# Three_Phase_Inverter_Based_on_IR2111_Gat.net
KiCad netlist of a schematic drawn in Altium Designer
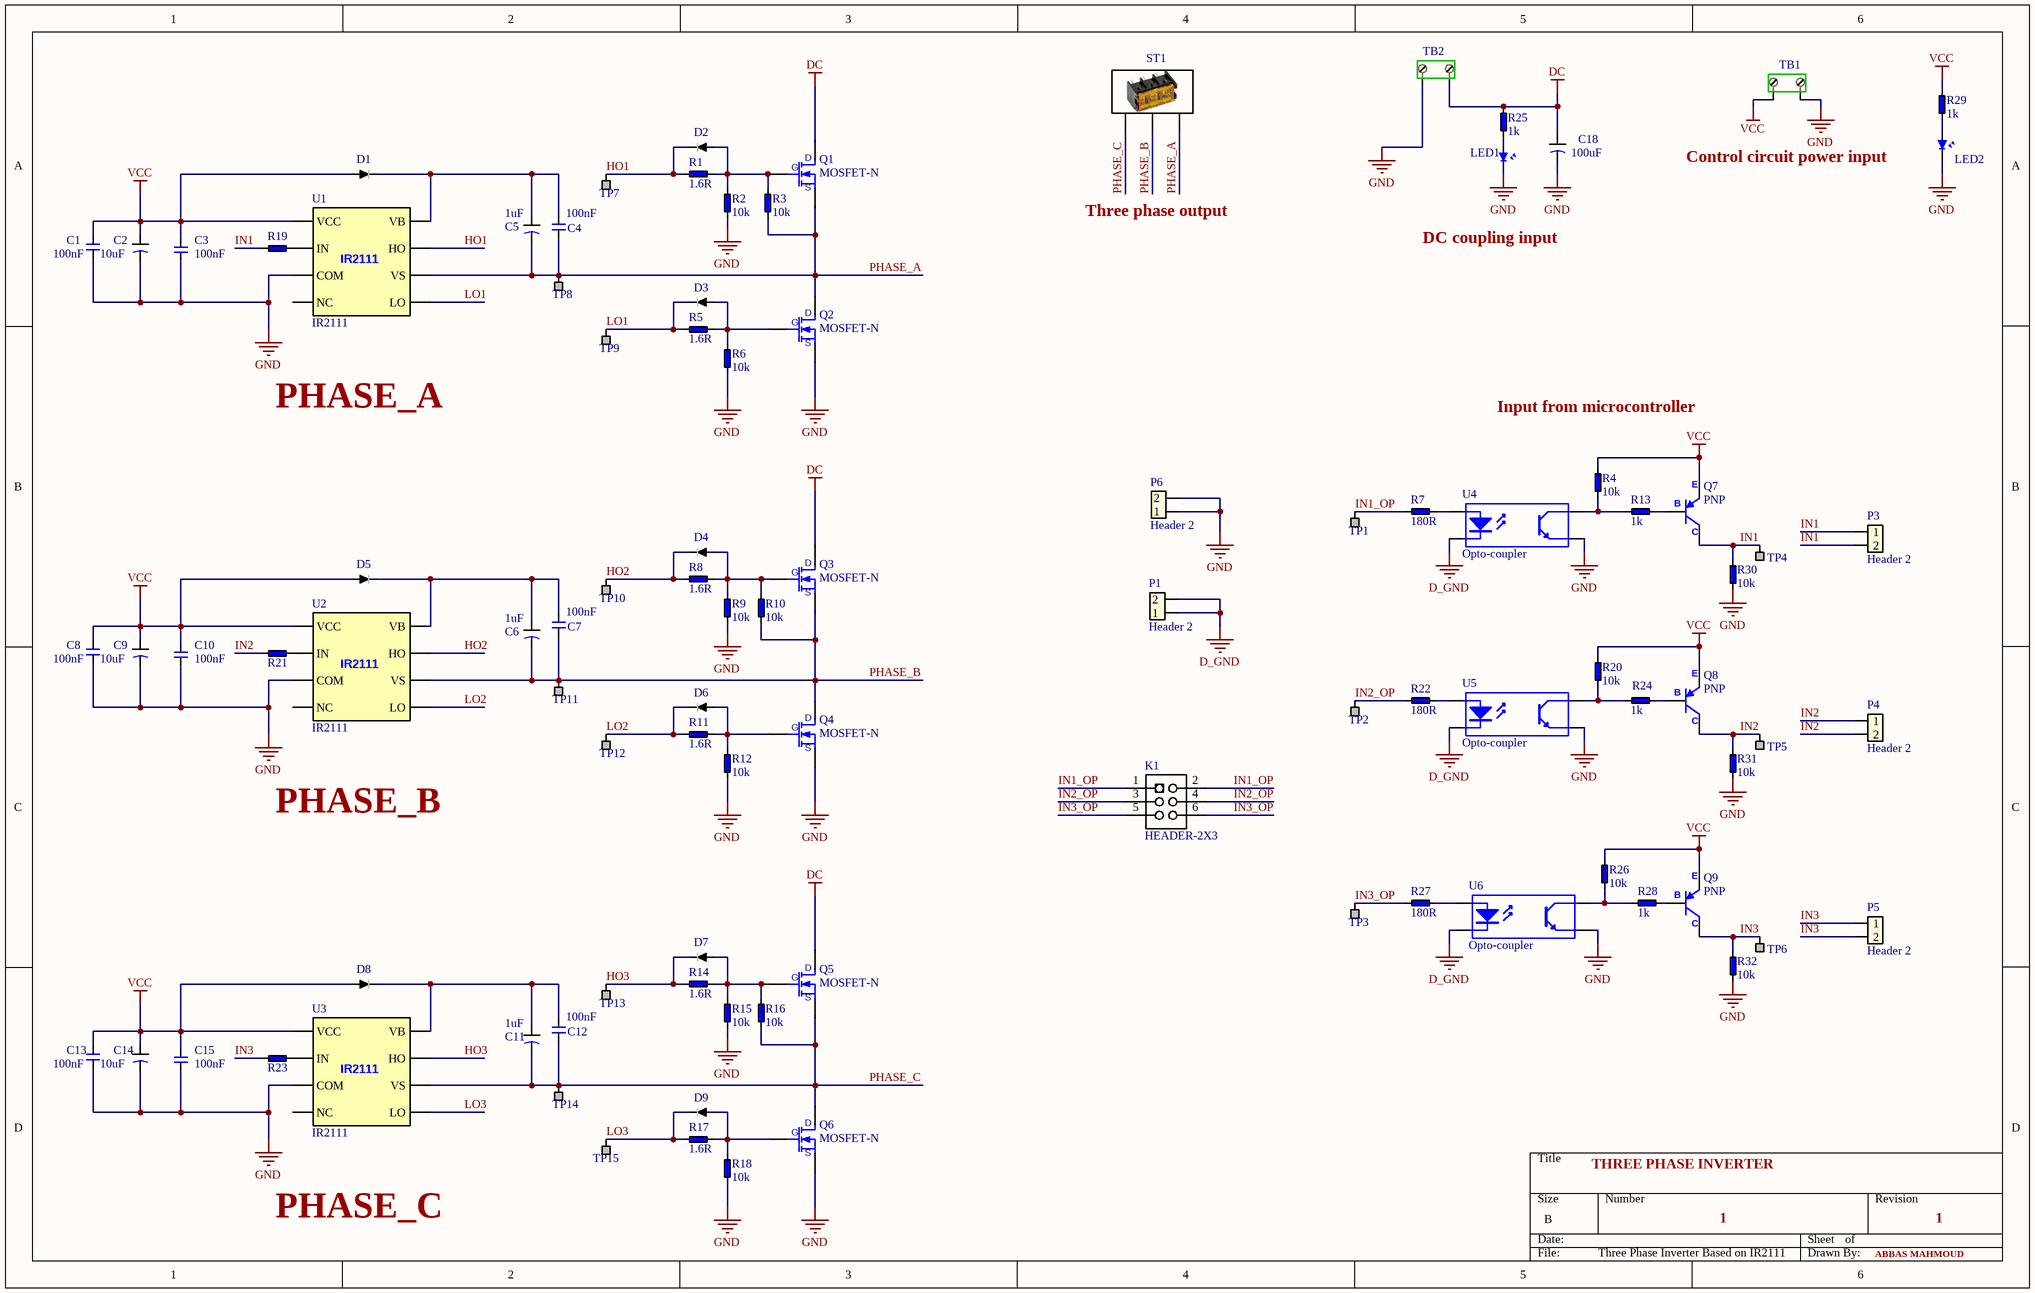
[diagram p0: Three Phase Inverter Based on IR2111 Gate Driver.SchDoc]

(export (version "E")
  (design (tool "Eeschema 10.0.6"))
  (components
    (comp (ref "C1")
      (value "100nF")
      (footprint "CCAP 0.1 P Y")
      (libsource (lib "Altium_Abbas") (part "CERAMIC CAP"))
    )
    (comp (ref "C2")
      (value "10uF")
      (footprint "ECAP 5X11X2MM")
      (libsource (lib "Altium_Abbas") (part "CAP POL"))
    )
    (comp (ref "C3")
      (value "100nF")
      (footprint "CCAP 0.1 P Y")
      (libsource (lib "Altium_Abbas") (part "CERAMIC CAP"))
    )
    (comp (ref "C4")
      (value "100nF")
      (footprint "CCAP 0.1 P Y")
      (libsource (lib "Altium_Abbas") (part "CERAMIC CAP"))
    )
    (comp (ref "C5")
      (value "1uF")
      (footprint "ECAP 5X11X2MM")
      (libsource (lib "Altium_Abbas") (part "CAP POL"))
    )
    (comp (ref "C6")
      (value "1uF")
      (footprint "ECAP 5X11X2MM")
      (libsource (lib "Altium_Abbas") (part "CAP POL"))
    )
    (comp (ref "C7")
      (value "100nF")
      (footprint "CCAP 0.1 P Y")
      (libsource (lib "Altium_Abbas") (part "CERAMIC CAP"))
    )
    (comp (ref "C8")
      (value "100nF")
      (footprint "CCAP 0.1 P Y")
      (libsource (lib "Altium_Abbas") (part "CERAMIC CAP"))
    )
    (comp (ref "C9")
      (value "10uF")
      (footprint "ECAP 5X11X2MM")
      (libsource (lib "Altium_Abbas") (part "CAP POL"))
    )
    (comp (ref "C10")
      (value "100nF")
      (footprint "CCAP 0.1 P Y")
      (libsource (lib "Altium_Abbas") (part "CERAMIC CAP"))
    )
    (comp (ref "C11")
      (value "1uF")
      (footprint "ECAP 5X11X2MM")
      (libsource (lib "Altium_Abbas") (part "CAP POL"))
    )
    (comp (ref "C12")
      (value "100nF")
      (footprint "CCAP 0.1 P Y")
      (libsource (lib "Altium_Abbas") (part "CERAMIC CAP"))
    )
    (comp (ref "C13")
      (value "100nF")
      (footprint "CCAP 0.1 P Y")
      (libsource (lib "Altium_Abbas") (part "CERAMIC CAP"))
    )
    (comp (ref "C14")
      (value "10uF")
      (footprint "ECAP 5X11X2MM")
      (libsource (lib "Altium_Abbas") (part "CAP POL"))
    )
    (comp (ref "C15")
      (value "100nF")
      (footprint "CCAP 0.1 P Y")
      (libsource (lib "Altium_Abbas") (part "CERAMIC CAP"))
    )
    (comp (ref "C18")
      (value "100uF")
      (footprint "ECAP 10X20X5MM")
      (libsource (lib "Altium_Abbas") (part "CAP POL"))
    )
    (comp (ref "D1")
      (value "DIODE")
      (footprint "DIODE-1n400X_0.3")
      (libsource (lib "Altium_Abbas") (part "DIODE"))
    )
    (comp (ref "D2")
      (value "DIODE")
      (footprint "DIODE-1n400X_0.3")
      (libsource (lib "Altium_Abbas") (part "DIODE"))
    )
    (comp (ref "D3")
      (value "DIODE")
      (footprint "DIODE-1n400X_0.3")
      (libsource (lib "Altium_Abbas") (part "DIODE"))
    )
    (comp (ref "D4")
      (value "DIODE")
      (footprint "DIODE-1n400X_0.3")
      (libsource (lib "Altium_Abbas") (part "DIODE"))
    )
    (comp (ref "D5")
      (value "DIODE")
      (footprint "DIODE-1n400X_0.3")
      (libsource (lib "Altium_Abbas") (part "DIODE"))
    )
    (comp (ref "D6")
      (value "DIODE")
      (footprint "DIODE-1n400X_0.3")
      (libsource (lib "Altium_Abbas") (part "DIODE"))
    )
    (comp (ref "D7")
      (value "DIODE")
      (footprint "DIODE-1n400X_0.3")
      (libsource (lib "Altium_Abbas") (part "DIODE"))
    )
    (comp (ref "D8")
      (value "DIODE")
      (footprint "DIODE-1n400X_0.3")
      (libsource (lib "Altium_Abbas") (part "DIODE"))
    )
    (comp (ref "D9")
      (value "DIODE")
      (footprint "DIODE-1n400X_0.3")
      (libsource (lib "Altium_Abbas") (part "DIODE"))
    )
    (comp (ref "K1")
      (value "HEADER-2X3")
      (footprint "HEADER-2X3")
      (libsource (lib "vh_altium_library") (part "HEADER-2X3"))
    )
    (comp (ref "LED1") (value "LED") (footprint "LED 3MM RED") (libsource (lib "Altium_Abbas") (part "LED")))
    (comp (ref "LED2")
      (value "LED")
      (footprint "LED 5MM WHITE")
      (libsource (lib "Altium_Abbas") (part "LED"))
    )
    (comp (ref "P1")
      (value "Header 2")
      (footprint "PINHEADER X2")
      (description "Header, 2-Pin")
      (fields (field (name "PUBLISHER") "Altium Limited"))
      (libsource (lib "Altium_Abbas") (part "Header 2"))
    )
    (comp (ref "P3")
      (value "Header 2")
      (footprint "PINHEADER X2")
      (description "Header, 2-Pin")
      (fields (field (name "PUBLISHER") "Altium Limited"))
      (libsource (lib "") (part "Header 2_1"))
    )
    (comp (ref "P4")
      (value "Header 2")
      (footprint "PINHEADER X2")
      (description "Header, 2-Pin")
      (fields (field (name "PUBLISHER") "Altium Limited"))
      (libsource (lib "") (part "Header 2_1"))
    )
    (comp (ref "P5")
      (value "Header 2")
      (footprint "PINHEADER X2")
      (description "Header, 2-Pin")
      (fields (field (name "PUBLISHER") "Altium Limited"))
      (libsource (lib "") (part "Header 2_1"))
    )
    (comp (ref "P6")
      (value "Header 2")
      (footprint "PINHEADER X2")
      (description "Header, 2-Pin")
      (fields (field (name "PUBLISHER") "Altium Limited"))
      (libsource (lib "Altium_Abbas") (part "Header 2"))
    )
    (comp (ref "Q1")
      (value "MOSFET-N")
      (footprint "Transistor-Mosfet_N_power")
      (description "N CHANNEL MOSFET")
      (libsource (lib "Altium_Abbas") (part "MOSFET-N"))
    )
    (comp (ref "Q2")
      (value "MOSFET-N")
      (footprint "Transistor-Mosfet_N_power")
      (description "N CHANNEL MOSFET")
      (libsource (lib "Altium_Abbas") (part "MOSFET-N"))
    )
    (comp (ref "Q3")
      (value "MOSFET-N")
      (footprint "Transistor-Mosfet_N_power")
      (description "N CHANNEL MOSFET")
      (libsource (lib "Altium_Abbas") (part "MOSFET-N"))
    )
    (comp (ref "Q4")
      (value "MOSFET-N")
      (footprint "Transistor-Mosfet_N_power")
      (description "N CHANNEL MOSFET")
      (libsource (lib "Altium_Abbas") (part "MOSFET-N"))
    )
    (comp (ref "Q5")
      (value "MOSFET-N")
      (footprint "Transistor-Mosfet_N_power")
      (description "N CHANNEL MOSFET")
      (libsource (lib "Altium_Abbas") (part "MOSFET-N"))
    )
    (comp (ref "Q6")
      (value "MOSFET-N")
      (footprint "Transistor-Mosfet_N_power")
      (description "N CHANNEL MOSFET")
      (libsource (lib "Altium_Abbas") (part "MOSFET-N"))
    )
    (comp (ref "Q7")
      (value "PNP")
      (footprint "Transistor - duplicate3")
      (libsource (lib "Altium_Abbas") (part "PNP"))
    )
    (comp (ref "Q8")
      (value "PNP")
      (footprint "Transistor - duplicate3")
      (libsource (lib "Altium_Abbas") (part "PNP"))
    )
    (comp (ref "Q9")
      (value "PNP")
      (footprint "Transistor - duplicate3")
      (libsource (lib "Altium_Abbas") (part "PNP"))
    )
    (comp (ref "R1")
      (value "1.6R")
      (footprint "RESISTOR _1")
      (libsource (lib "Altium_Abbas") (part "RESISTOR"))
    )
    (comp (ref "R2")
      (value "10k")
      (footprint "RESISTOR _1")
      (libsource (lib "Altium_Abbas") (part "RESISTOR"))
    )
    (comp (ref "R3")
      (value "10k")
      (footprint "RESISTOR _1")
      (libsource (lib "Altium_Abbas") (part "RESISTOR"))
    )
    (comp (ref "R4")
      (value "10k")
      (footprint "RESISTOR _1")
      (libsource (lib "Altium_Abbas") (part "RESISTOR"))
    )
    (comp (ref "R5")
      (value "1.6R")
      (footprint "RESISTOR _1")
      (libsource (lib "Altium_Abbas") (part "RESISTOR"))
    )
    (comp (ref "R6")
      (value "10k")
      (footprint "RESISTOR _1")
      (libsource (lib "Altium_Abbas") (part "RESISTOR"))
    )
    (comp (ref "R7")
      (value "180R")
      (footprint "RESISTOR _1")
      (libsource (lib "Altium_Abbas") (part "RESISTOR"))
    )
    (comp (ref "R8")
      (value "1.6R")
      (footprint "RESISTOR _1")
      (libsource (lib "Altium_Abbas") (part "RESISTOR"))
    )
    (comp (ref "R9")
      (value "10k")
      (footprint "RESISTOR _1")
      (libsource (lib "Altium_Abbas") (part "RESISTOR"))
    )
    (comp (ref "R10")
      (value "10k")
      (footprint "RESISTOR _1")
      (libsource (lib "Altium_Abbas") (part "RESISTOR"))
    )
    (comp (ref "R11")
      (value "1.6R")
      (footprint "RESISTOR _1")
      (libsource (lib "Altium_Abbas") (part "RESISTOR"))
    )
    (comp (ref "R12")
      (value "10k")
      (footprint "RESISTOR _1")
      (libsource (lib "Altium_Abbas") (part "RESISTOR"))
    )
    (comp (ref "R13")
      (value "1k")
      (footprint "RESISTOR _1")
      (libsource (lib "Altium_Abbas") (part "RESISTOR"))
    )
    (comp (ref "R14")
      (value "1.6R")
      (footprint "RESISTOR _1")
      (libsource (lib "Altium_Abbas") (part "RESISTOR"))
    )
    (comp (ref "R15")
      (value "10k")
      (footprint "RESISTOR _1")
      (libsource (lib "Altium_Abbas") (part "RESISTOR"))
    )
    (comp (ref "R16")
      (value "10k")
      (footprint "RESISTOR _1")
      (libsource (lib "Altium_Abbas") (part "RESISTOR"))
    )
    (comp (ref "R17")
      (value "1.6R")
      (footprint "RESISTOR _1")
      (libsource (lib "Altium_Abbas") (part "RESISTOR"))
    )
    (comp (ref "R18")
      (value "10k")
      (footprint "RESISTOR _1")
      (libsource (lib "Altium_Abbas") (part "RESISTOR"))
    )
    (comp (ref "R19")
      (value "1k")
      (footprint "RESISTOR _1")
      (libsource (lib "Altium_Abbas") (part "RESISTOR"))
    )
    (comp (ref "R20")
      (value "10k")
      (footprint "RESISTOR _1")
      (libsource (lib "Altium_Abbas") (part "RESISTOR"))
    )
    (comp (ref "R21")
      (value "1k")
      (footprint "RESISTOR _1")
      (libsource (lib "Altium_Abbas") (part "RESISTOR"))
    )
    (comp (ref "R22")
      (value "180R")
      (footprint "RESISTOR _1")
      (libsource (lib "Altium_Abbas") (part "RESISTOR"))
    )
    (comp (ref "R23")
      (value "1k")
      (footprint "RESISTOR _1")
      (libsource (lib "Altium_Abbas") (part "RESISTOR"))
    )
    (comp (ref "R24")
      (value "1k")
      (footprint "RESISTOR _1")
      (libsource (lib "Altium_Abbas") (part "RESISTOR"))
    )
    (comp (ref "R25")
      (value "1k")
      (footprint "RESISTOR _9")
      (libsource (lib "Altium_Abbas") (part "RESISTOR"))
    )
    (comp (ref "R26")
      (value "10k")
      (footprint "RESISTOR _1")
      (libsource (lib "Altium_Abbas") (part "RESISTOR"))
    )
    (comp (ref "R27")
      (value "180R")
      (footprint "RESISTOR _1")
      (libsource (lib "Altium_Abbas") (part "RESISTOR"))
    )
    (comp (ref "R28")
      (value "1k")
      (footprint "RESISTOR _1")
      (libsource (lib "Altium_Abbas") (part "RESISTOR"))
    )
    (comp (ref "R29")
      (value "1k")
      (footprint "RESISTOR _9")
      (libsource (lib "Altium_Abbas") (part "RESISTOR"))
    )
    (comp (ref "R30")
      (value "10k")
      (footprint "RESISTOR _1")
      (libsource (lib "Altium_Abbas") (part "RESISTOR"))
    )
    (comp (ref "R31")
      (value "10k")
      (footprint "RESISTOR _1")
      (libsource (lib "Altium_Abbas") (part "RESISTOR"))
    )
    (comp (ref "R32")
      (value "10k")
      (footprint "RESISTOR _1")
      (libsource (lib "Altium_Abbas") (part "RESISTOR"))
    )
    (comp (ref "ST1")
      (value "SCREW TERMINAL x3")
      (footprint "SCREW TERMINAL  x3")
      (description "Barrier Terminal Block 3 Pin with cover 300V/25A")
      (libsource (lib "Altium_Abbas") (part "SCREW TERMINAL x3"))
    )
    (comp (ref "TB1")
      (value "Terminal block 2 pin")
      (footprint "AK500/2 - pluggable")
      (description "Terminal Block 2 Pin 10A 300V")
      (libsource (lib "Altium_Abbas") (part "Terminal block 2 pin"))
    )
    (comp (ref "TB2")
      (value "Terminal block 2 pin")
      (footprint "AK500/2 - pluggable")
      (description "Terminal Block 2 Pin 10A 300V")
      (libsource (lib "Altium_Abbas") (part "Terminal block 2 pin"))
    )
    (comp (ref "TP1")
      (value "TESTPIN")
      (footprint "TESTPIN")
      (description "TESTPIN SINGLE PIN HEADER")
      (libsource (lib "vh_altium_library") (part "TESTPIN"))
    )
    (comp (ref "TP2")
      (value "TESTPIN")
      (footprint "TESTPIN")
      (description "TESTPIN SINGLE PIN HEADER")
      (libsource (lib "vh_altium_library") (part "TESTPIN"))
    )
    (comp (ref "TP3")
      (value "TESTPIN")
      (footprint "TESTPIN")
      (description "TESTPIN SINGLE PIN HEADER")
      (libsource (lib "vh_altium_library") (part "TESTPIN"))
    )
    (comp (ref "TP4")
      (value "TESTPIN")
      (footprint "TESTPIN")
      (description "TESTPIN SINGLE PIN HEADER")
      (libsource (lib "vh_altium_library") (part "TESTPIN"))
    )
    (comp (ref "TP5")
      (value "TESTPIN")
      (footprint "TESTPIN")
      (description "TESTPIN SINGLE PIN HEADER")
      (libsource (lib "vh_altium_library") (part "TESTPIN"))
    )
    (comp (ref "TP6")
      (value "TESTPIN")
      (footprint "TESTPIN")
      (description "TESTPIN SINGLE PIN HEADER")
      (libsource (lib "vh_altium_library") (part "TESTPIN"))
    )
    (comp (ref "TP7")
      (value "TESTPIN")
      (footprint "TESTPIN")
      (description "TESTPIN SINGLE PIN HEADER")
      (libsource (lib "vh_altium_library") (part "TESTPIN"))
    )
    (comp (ref "TP8")
      (value "TESTPIN")
      (footprint "TESTPIN")
      (description "TESTPIN SINGLE PIN HEADER")
      (libsource (lib "vh_altium_library") (part "TESTPIN"))
    )
    (comp (ref "TP9")
      (value "TESTPIN")
      (footprint "TESTPIN")
      (description "TESTPIN SINGLE PIN HEADER")
      (libsource (lib "vh_altium_library") (part "TESTPIN"))
    )
    (comp (ref "TP10")
      (value "TESTPIN")
      (footprint "TESTPIN")
      (description "TESTPIN SINGLE PIN HEADER")
      (libsource (lib "vh_altium_library") (part "TESTPIN"))
    )
    (comp (ref "TP11")
      (value "TESTPIN")
      (footprint "TESTPIN")
      (description "TESTPIN SINGLE PIN HEADER")
      (libsource (lib "vh_altium_library") (part "TESTPIN"))
    )
    (comp (ref "TP12")
      (value "TESTPIN")
      (footprint "TESTPIN")
      (description "TESTPIN SINGLE PIN HEADER")
      (libsource (lib "vh_altium_library") (part "TESTPIN"))
    )
    (comp (ref "TP13")
      (value "TESTPIN")
      (footprint "TESTPIN")
      (description "TESTPIN SINGLE PIN HEADER")
      (libsource (lib "vh_altium_library") (part "TESTPIN"))
    )
    (comp (ref "TP14")
      (value "TESTPIN")
      (footprint "TESTPIN")
      (description "TESTPIN SINGLE PIN HEADER")
      (libsource (lib "vh_altium_library") (part "TESTPIN"))
    )
    (comp (ref "TP15")
      (value "TESTPIN")
      (footprint "TESTPIN")
      (description "TESTPIN SINGLE PIN HEADER")
      (libsource (lib "vh_altium_library") (part "TESTPIN"))
    )
    (comp (ref "U1")
      (value "IR2111")
      (footprint "IC X8 PIN")
      (description "HALF-BRIDGE DRIVER")
      (libsource (lib "Altium_Abbas") (part "IR2111"))
    )
    (comp (ref "U2")
      (value "IR2111")
      (footprint "IC X8 PIN")
      (description "HALF-BRIDGE DRIVER")
      (libsource (lib "Altium_Abbas") (part "IR2111"))
    )
    (comp (ref "U3")
      (value "IR2111")
      (footprint "IC X8 PIN")
      (description "HALF-BRIDGE DRIVER")
      (libsource (lib "Altium_Abbas") (part "IR2111"))
    )
    (comp (ref "U4")
      (value "Opto-coupler")
      (footprint "IC X4 PIN")
      (description "4-Pin Phototransistor Optocoupler")
      (fields (field (name "PUBLISHER") "Altium Limited"))
      (libsource (lib "Altium_Abbas") (part "Opto-coupler"))
    )
    (comp (ref "U5")
      (value "Opto-coupler")
      (footprint "IC X4 PIN")
      (description "4-Pin Phototransistor Optocoupler")
      (fields (field (name "PUBLISHER") "Altium Limited"))
      (libsource (lib "Altium_Abbas") (part "Opto-coupler"))
    )
    (comp (ref "U6")
      (value "Opto-coupler")
      (footprint "IC X4 PIN")
      (description "4-Pin Phototransistor Optocoupler")
      (fields (field (name "PUBLISHER") "Altium Limited"))
      (libsource (lib "Altium_Abbas") (part "Opto-coupler"))
    )
  )
  (nets
    (net (code "1") (name "/HO1") (class "Default")
      (node (ref "D2") (pin "K") (pintype "passive"))
      (node (ref "R1") (pin "1") (pinfunction "5_1") (pintype "passive"))
      (node (ref "TP7") (pin "1") (pinfunction "1_1") (pintype "passive"))
      (node (ref "U1") (pin "7") (pinfunction "HO_7") (pintype "passive"))
    )
    (net (code "2") (name "/HO2") (class "Default")
      (node (ref "D4") (pin "K") (pintype "passive"))
      (node (ref "R8") (pin "1") (pinfunction "5_1") (pintype "passive"))
      (node (ref "TP10") (pin "1") (pinfunction "1_1") (pintype "passive"))
      (node (ref "U2") (pin "7") (pinfunction "HO_7") (pintype "passive"))
    )
    (net (code "3") (name "/HO3") (class "Default")
      (node (ref "D7") (pin "K") (pintype "passive"))
      (node (ref "R14") (pin "1") (pinfunction "5_1") (pintype "passive"))
      (node (ref "TP13") (pin "1") (pinfunction "1_1") (pintype "passive"))
      (node (ref "U3") (pin "7") (pinfunction "HO_7") (pintype "passive"))
    )
    (net (code "4") (name "/IN1") (class "Default")
      (node (ref "P3") (pin "1") (pinfunction "1_1") (pintype "passive"))
      (node (ref "P3") (pin "2") (pinfunction "2_2") (pintype "passive"))
      (node (ref "Q7") (pin "3") (pinfunction "C_3") (pintype "passive"))
      (node (ref "R19") (pin "1") (pinfunction "5_1") (pintype "passive"))
      (node (ref "R30") (pin "1") (pinfunction "5_1") (pintype "passive"))
      (node (ref "TP4") (pin "1") (pinfunction "1_1") (pintype "passive"))
    )
    (net (code "5") (name "/IN1_OP") (class "Default")
      (node (ref "K1") (pin "1") (pintype "passive"))
      (node (ref "K1") (pin "2") (pintype "passive"))
      (node (ref "R7") (pin "1") (pinfunction "5_1") (pintype "passive"))
      (node (ref "TP1") (pin "1") (pinfunction "1_1") (pintype "passive"))
    )
    (net (code "6") (name "/IN2") (class "Default")
      (node (ref "P4") (pin "1") (pinfunction "1_1") (pintype "passive"))
      (node (ref "P4") (pin "2") (pinfunction "2_2") (pintype "passive"))
      (node (ref "Q8") (pin "3") (pinfunction "C_3") (pintype "passive"))
      (node (ref "R21") (pin "1") (pinfunction "5_1") (pintype "passive"))
      (node (ref "R31") (pin "1") (pinfunction "5_1") (pintype "passive"))
      (node (ref "TP5") (pin "1") (pinfunction "1_1") (pintype "passive"))
    )
    (net (code "7") (name "/IN2_OP") (class "Default")
      (node (ref "K1") (pin "3") (pintype "passive"))
      (node (ref "K1") (pin "4") (pintype "passive"))
      (node (ref "R22") (pin "1") (pinfunction "5_1") (pintype "passive"))
      (node (ref "TP2") (pin "1") (pinfunction "1_1") (pintype "passive"))
    )
    (net (code "8") (name "/IN3") (class "Default")
      (node (ref "P5") (pin "1") (pinfunction "1_1") (pintype "passive"))
      (node (ref "P5") (pin "2") (pinfunction "2_2") (pintype "passive"))
      (node (ref "Q9") (pin "3") (pinfunction "C_3") (pintype "passive"))
      (node (ref "R23") (pin "1") (pinfunction "5_1") (pintype "passive"))
      (node (ref "R32") (pin "1") (pinfunction "5_1") (pintype "passive"))
      (node (ref "TP6") (pin "1") (pinfunction "1_1") (pintype "passive"))
    )
    (net (code "9") (name "/IN3_OP") (class "Default")
      (node (ref "K1") (pin "5") (pintype "passive"))
      (node (ref "K1") (pin "6") (pintype "passive"))
      (node (ref "R27") (pin "1") (pinfunction "5_1") (pintype "passive"))
      (node (ref "TP3") (pin "1") (pinfunction "1_1") (pintype "passive"))
    )
    (net (code "10") (name "/LO1") (class "Default")
      (node (ref "D3") (pin "K") (pintype "passive"))
      (node (ref "R5") (pin "1") (pinfunction "5_1") (pintype "passive"))
      (node (ref "TP9") (pin "1") (pinfunction "1_1") (pintype "passive"))
      (node (ref "U1") (pin "4") (pinfunction "LO_4") (pintype "passive"))
    )
    (net (code "11") (name "/LO2") (class "Default")
      (node (ref "D6") (pin "K") (pintype "passive"))
      (node (ref "R11") (pin "1") (pinfunction "5_1") (pintype "passive"))
      (node (ref "TP12") (pin "1") (pinfunction "1_1") (pintype "passive"))
      (node (ref "U2") (pin "4") (pinfunction "LO_4") (pintype "passive"))
    )
    (net (code "12") (name "/LO3") (class "Default")
      (node (ref "D9") (pin "K") (pintype "passive"))
      (node (ref "R17") (pin "1") (pinfunction "5_1") (pintype "passive"))
      (node (ref "TP15") (pin "1") (pinfunction "1_1") (pintype "passive"))
      (node (ref "U3") (pin "4") (pinfunction "LO_4") (pintype "passive"))
    )
    (net (code "13") (name "/PHASE_A") (class "Default")
      (node (ref "C4") (pin "2") (pintype "passive"))
      (node (ref "C5") (pin "K") (pintype "passive"))
      (node (ref "Q1") (pin "3") (pinfunction "S_3") (pintype "passive"))
      (node (ref "Q2") (pin "2") (pinfunction "D_2") (pintype "passive"))
      (node (ref "R3") (pin "1") (pinfunction "5_1") (pintype "passive"))
      (node (ref "ST1") (pin "3") (pinfunction "3_3") (pintype "passive"))
      (node (ref "TP8") (pin "1") (pinfunction "1_1") (pintype "passive"))
      (node (ref "U1") (pin "6") (pinfunction "VS_6") (pintype "passive"))
    )
    (net (code "14") (name "/PHASE_B") (class "Default")
      (node (ref "C6") (pin "K") (pintype "passive"))
      (node (ref "C7") (pin "2") (pintype "passive"))
      (node (ref "Q3") (pin "3") (pinfunction "S_3") (pintype "passive"))
      (node (ref "Q4") (pin "2") (pinfunction "D_2") (pintype "passive"))
      (node (ref "R10") (pin "1") (pinfunction "5_1") (pintype "passive"))
      (node (ref "ST1") (pin "2") (pinfunction "2_2") (pintype "passive"))
      (node (ref "TP11") (pin "1") (pinfunction "1_1") (pintype "passive"))
      (node (ref "U2") (pin "6") (pinfunction "VS_6") (pintype "passive"))
    )
    (net (code "15") (name "/PHASE_C") (class "Default")
      (node (ref "C11") (pin "K") (pintype "passive"))
      (node (ref "C12") (pin "2") (pintype "passive"))
      (node (ref "Q5") (pin "3") (pinfunction "S_3") (pintype "passive"))
      (node (ref "Q6") (pin "2") (pinfunction "D_2") (pintype "passive"))
      (node (ref "R16") (pin "1") (pinfunction "5_1") (pintype "passive"))
      (node (ref "ST1") (pin "1") (pinfunction "1_1") (pintype "passive"))
      (node (ref "TP14") (pin "1") (pinfunction "1_1") (pintype "passive"))
      (node (ref "U3") (pin "6") (pinfunction "VS_6") (pintype "passive"))
    )
    (net (code "16") (name "DC") (class "Default")
      (node (ref "C18") (pin "A") (pintype "passive"))
      (node (ref "Q1") (pin "2") (pinfunction "D_2") (pintype "passive"))
      (node (ref "Q3") (pin "2") (pinfunction "D_2") (pintype "passive"))
      (node (ref "Q5") (pin "2") (pinfunction "D_2") (pintype "passive"))
      (node (ref "R25") (pin "2") (pinfunction "6_2") (pintype "passive"))
      (node (ref "TB2") (pin "1") (pinfunction "*_1") (pintype "passive"))
    )
    (net (code "17") (name "D_GND") (class "Default")
      (node (ref "P1") (pin "1") (pinfunction "1_1") (pintype "passive"))
      (node (ref "P1") (pin "2") (pinfunction "2_2") (pintype "passive"))
      (node (ref "U4") (pin "2") (pinfunction "K_2") (pintype "passive"))
      (node (ref "U5") (pin "2") (pinfunction "K_2") (pintype "passive"))
      (node (ref "U6") (pin "2") (pinfunction "K_2") (pintype "passive"))
    )
    (net (code "18") (name "GND") (class "Default")
      (node (ref "C1") (pin "2") (pintype "passive"))
      (node (ref "C10") (pin "2") (pintype "passive"))
      (node (ref "C13") (pin "2") (pintype "passive"))
      (node (ref "C14") (pin "K") (pintype "passive"))
      (node (ref "C15") (pin "2") (pintype "passive"))
      (node (ref "C18") (pin "K") (pintype "passive"))
      (node (ref "C2") (pin "K") (pintype "passive"))
      (node (ref "C3") (pin "2") (pintype "passive"))
      (node (ref "C8") (pin "2") (pintype "passive"))
      (node (ref "C9") (pin "K") (pintype "passive"))
      (node (ref "LED1") (pin "K") (pintype "passive"))
      (node (ref "LED2") (pin "K") (pintype "passive"))
      (node (ref "P6") (pin "1") (pinfunction "1_1") (pintype "passive"))
      (node (ref "P6") (pin "2") (pinfunction "2_2") (pintype "passive"))
      (node (ref "Q2") (pin "3") (pinfunction "S_3") (pintype "passive"))
      (node (ref "Q4") (pin "3") (pinfunction "S_3") (pintype "passive"))
      (node (ref "Q6") (pin "3") (pinfunction "S_3") (pintype "passive"))
      (node (ref "R12") (pin "1") (pinfunction "5_1") (pintype "passive"))
      (node (ref "R15") (pin "1") (pinfunction "5_1") (pintype "passive"))
      (node (ref "R18") (pin "1") (pinfunction "5_1") (pintype "passive"))
      (node (ref "R2") (pin "1") (pinfunction "5_1") (pintype "passive"))
      (node (ref "R30") (pin "2") (pinfunction "6_2") (pintype "passive"))
      (node (ref "R31") (pin "2") (pinfunction "6_2") (pintype "passive"))
      (node (ref "R32") (pin "2") (pinfunction "6_2") (pintype "passive"))
      (node (ref "R6") (pin "1") (pinfunction "5_1") (pintype "passive"))
      (node (ref "R9") (pin "1") (pinfunction "5_1") (pintype "passive"))
      (node (ref "TB1") (pin "1") (pinfunction "*_1") (pintype "passive"))
      (node (ref "TB2") (pin "2") (pinfunction "*_2") (pintype "passive"))
      (node (ref "U1") (pin "3") (pinfunction "COM_3") (pintype "passive"))
      (node (ref "U2") (pin "3") (pinfunction "COM_3") (pintype "passive"))
      (node (ref "U3") (pin "3") (pinfunction "COM_3") (pintype "passive"))
      (node (ref "U4") (pin "3") (pinfunction "E_3") (pintype "passive"))
      (node (ref "U5") (pin "3") (pinfunction "E_3") (pintype "passive"))
      (node (ref "U6") (pin "3") (pinfunction "E_3") (pintype "passive"))
    )
    (net (code "19") (name "Net-(Q1-G)") (class "Default")
      (node (ref "D2") (pin "A") (pintype "passive"))
      (node (ref "Q1") (pin "1") (pinfunction "G_1") (pintype "passive"))
      (node (ref "R1") (pin "2") (pinfunction "6_2") (pintype "passive"))
      (node (ref "R2") (pin "2") (pinfunction "6_2") (pintype "passive"))
      (node (ref "R3") (pin "2") (pinfunction "6_2") (pintype "passive"))
    )
    (net (code "20") (name "Net-(Q2-G)") (class "Default")
      (node (ref "D3") (pin "A") (pintype "passive"))
      (node (ref "Q2") (pin "1") (pinfunction "G_1") (pintype "passive"))
      (node (ref "R5") (pin "2") (pinfunction "6_2") (pintype "passive"))
      (node (ref "R6") (pin "2") (pinfunction "6_2") (pintype "passive"))
    )
    (net (code "21") (name "Net-(Q3-G)") (class "Default")
      (node (ref "D4") (pin "A") (pintype "passive"))
      (node (ref "Q3") (pin "1") (pinfunction "G_1") (pintype "passive"))
      (node (ref "R10") (pin "2") (pinfunction "6_2") (pintype "passive"))
      (node (ref "R8") (pin "2") (pinfunction "6_2") (pintype "passive"))
      (node (ref "R9") (pin "2") (pinfunction "6_2") (pintype "passive"))
    )
    (net (code "22") (name "Net-(Q4-G)") (class "Default")
      (node (ref "D6") (pin "A") (pintype "passive"))
      (node (ref "Q4") (pin "1") (pinfunction "G_1") (pintype "passive"))
      (node (ref "R11") (pin "2") (pinfunction "6_2") (pintype "passive"))
      (node (ref "R12") (pin "2") (pinfunction "6_2") (pintype "passive"))
    )
    (net (code "23") (name "Net-(Q5-G)") (class "Default")
      (node (ref "D7") (pin "A") (pintype "passive"))
      (node (ref "Q5") (pin "1") (pinfunction "G_1") (pintype "passive"))
      (node (ref "R14") (pin "2") (pinfunction "6_2") (pintype "passive"))
      (node (ref "R15") (pin "2") (pinfunction "6_2") (pintype "passive"))
      (node (ref "R16") (pin "2") (pinfunction "6_2") (pintype "passive"))
    )
    (net (code "24") (name "Net-(Q6-G)") (class "Default")
      (node (ref "D9") (pin "A") (pintype "passive"))
      (node (ref "Q6") (pin "1") (pinfunction "G_1") (pintype "passive"))
      (node (ref "R17") (pin "2") (pinfunction "6_2") (pintype "passive"))
      (node (ref "R18") (pin "2") (pinfunction "6_2") (pintype "passive"))
    )
    (net (code "25") (name "Net-(Q7-B)") (class "Default")
      (node (ref "Q7") (pin "2") (pinfunction "B_2") (pintype "passive"))
      (node (ref "R13") (pin "2") (pinfunction "6_2") (pintype "passive"))
    )
    (net (code "26") (name "Net-(Q8-B)") (class "Default")
      (node (ref "Q8") (pin "2") (pinfunction "B_2") (pintype "passive"))
      (node (ref "R24") (pin "2") (pinfunction "6_2") (pintype "passive"))
    )
    (net (code "27") (name "Net-(Q9-B)") (class "Default")
      (node (ref "Q9") (pin "2") (pinfunction "B_2") (pintype "passive"))
      (node (ref "R28") (pin "2") (pinfunction "6_2") (pintype "passive"))
    )
    (net (code "28") (name "Net-(R7-6)") (class "Default")
      (node (ref "R7") (pin "2") (pinfunction "6_2") (pintype "passive"))
      (node (ref "U4") (pin "1") (pinfunction "A_1") (pintype "passive"))
    )
    (net (code "29") (name "Net-(R13-5)") (class "Default")
      (node (ref "R13") (pin "1") (pinfunction "5_1") (pintype "passive"))
      (node (ref "R4") (pin "1") (pinfunction "5_1") (pintype "passive"))
      (node (ref "U4") (pin "4") (pinfunction "C_4") (pintype "passive"))
    )
    (net (code "30") (name "Net-(R19-6)") (class "Default")
      (node (ref "R19") (pin "2") (pinfunction "6_2") (pintype "passive"))
      (node (ref "U1") (pin "2") (pinfunction "IN_2") (pintype "passive"))
    )
    (net (code "31") (name "Net-(R20-5)") (class "Default")
      (node (ref "R20") (pin "1") (pinfunction "5_1") (pintype "passive"))
      (node (ref "R24") (pin "1") (pinfunction "5_1") (pintype "passive"))
      (node (ref "U5") (pin "4") (pinfunction "C_4") (pintype "passive"))
    )
    (net (code "32") (name "Net-(R21-6)") (class "Default")
      (node (ref "R21") (pin "2") (pinfunction "6_2") (pintype "passive"))
      (node (ref "U2") (pin "2") (pinfunction "IN_2") (pintype "passive"))
    )
    (net (code "33") (name "Net-(R22-6)") (class "Default")
      (node (ref "R22") (pin "2") (pinfunction "6_2") (pintype "passive"))
      (node (ref "U5") (pin "1") (pinfunction "A_1") (pintype "passive"))
    )
    (net (code "34") (name "Net-(R23-6)") (class "Default")
      (node (ref "R23") (pin "2") (pinfunction "6_2") (pintype "passive"))
      (node (ref "U3") (pin "2") (pinfunction "IN_2") (pintype "passive"))
    )
    (net (code "35") (name "Net-(R25-5)") (class "Default")
      (node (ref "LED1") (pin "A") (pintype "passive"))
      (node (ref "R25") (pin "1") (pinfunction "5_1") (pintype "passive"))
    )
    (net (code "36") (name "Net-(R26-5)") (class "Default")
      (node (ref "R26") (pin "1") (pinfunction "5_1") (pintype "passive"))
      (node (ref "R28") (pin "1") (pinfunction "5_1") (pintype "passive"))
      (node (ref "U6") (pin "4") (pinfunction "C_4") (pintype "passive"))
    )
    (net (code "37") (name "Net-(R27-6)") (class "Default")
      (node (ref "R27") (pin "2") (pinfunction "6_2") (pintype "passive"))
      (node (ref "U6") (pin "1") (pinfunction "A_1") (pintype "passive"))
    )
    (net (code "38") (name "Net-(R29-5)") (class "Default")
      (node (ref "LED2") (pin "A") (pintype "passive"))
      (node (ref "R29") (pin "1") (pinfunction "5_1") (pintype "passive"))
    )
    (net (code "39") (name "Net-(U1-VB)") (class "Default")
      (node (ref "C4") (pin "1") (pintype "passive"))
      (node (ref "C5") (pin "A") (pintype "passive"))
      (node (ref "D1") (pin "K") (pintype "passive"))
      (node (ref "U1") (pin "8") (pinfunction "VB_8") (pintype "passive"))
    )
    (net (code "40") (name "Net-(U2-VB)") (class "Default")
      (node (ref "C6") (pin "A") (pintype "passive"))
      (node (ref "C7") (pin "1") (pintype "passive"))
      (node (ref "D5") (pin "K") (pintype "passive"))
      (node (ref "U2") (pin "8") (pinfunction "VB_8") (pintype "passive"))
    )
    (net (code "41") (name "Net-(U3-VB)") (class "Default")
      (node (ref "C11") (pin "A") (pintype "passive"))
      (node (ref "C12") (pin "1") (pintype "passive"))
      (node (ref "D8") (pin "K") (pintype "passive"))
      (node (ref "U3") (pin "8") (pinfunction "VB_8") (pintype "passive"))
    )
    (net (code "42") (name "VCC") (class "Default")
      (node (ref "C1") (pin "1") (pintype "passive"))
      (node (ref "C10") (pin "1") (pintype "passive"))
      (node (ref "C13") (pin "1") (pintype "passive"))
      (node (ref "C14") (pin "A") (pintype "passive"))
      (node (ref "C15") (pin "1") (pintype "passive"))
      (node (ref "C2") (pin "A") (pintype "passive"))
      (node (ref "C3") (pin "1") (pintype "passive"))
      (node (ref "C8") (pin "1") (pintype "passive"))
      (node (ref "C9") (pin "A") (pintype "passive"))
      (node (ref "D1") (pin "A") (pintype "passive"))
      (node (ref "D5") (pin "A") (pintype "passive"))
      (node (ref "D8") (pin "A") (pintype "passive"))
      (node (ref "Q7") (pin "1") (pinfunction "E_1") (pintype "passive"))
      (node (ref "Q8") (pin "1") (pinfunction "E_1") (pintype "passive"))
      (node (ref "Q9") (pin "1") (pinfunction "E_1") (pintype "passive"))
      (node (ref "R20") (pin "2") (pinfunction "6_2") (pintype "passive"))
      (node (ref "R26") (pin "2") (pinfunction "6_2") (pintype "passive"))
      (node (ref "R29") (pin "2") (pinfunction "6_2") (pintype "passive"))
      (node (ref "R4") (pin "2") (pinfunction "6_2") (pintype "passive"))
      (node (ref "TB1") (pin "2") (pinfunction "*_2") (pintype "passive"))
      (node (ref "U1") (pin "1") (pinfunction "VCC_1") (pintype "passive"))
      (node (ref "U2") (pin "1") (pinfunction "VCC_1") (pintype "passive"))
      (node (ref "U3") (pin "1") (pinfunction "VCC_1") (pintype "passive"))
    )
    (net (code "43") (name "unconnected-(U1-NC-Pad5)") (class "Default")
      (node (ref "U1") (pin "5") (pinfunction "NC_5") (pintype "passive"))
    )
    (net (code "44") (name "unconnected-(U2-NC-Pad5)") (class "Default")
      (node (ref "U2") (pin "5") (pinfunction "NC_5") (pintype "passive"))
    )
    (net (code "45") (name "unconnected-(U3-NC-Pad5)") (class "Default")
      (node (ref "U3") (pin "5") (pinfunction "NC_5") (pintype "passive"))
    )
  )
)
